# LiFePO4_Charger.net
KiCad netlist of a schematic drawn in EAGLE
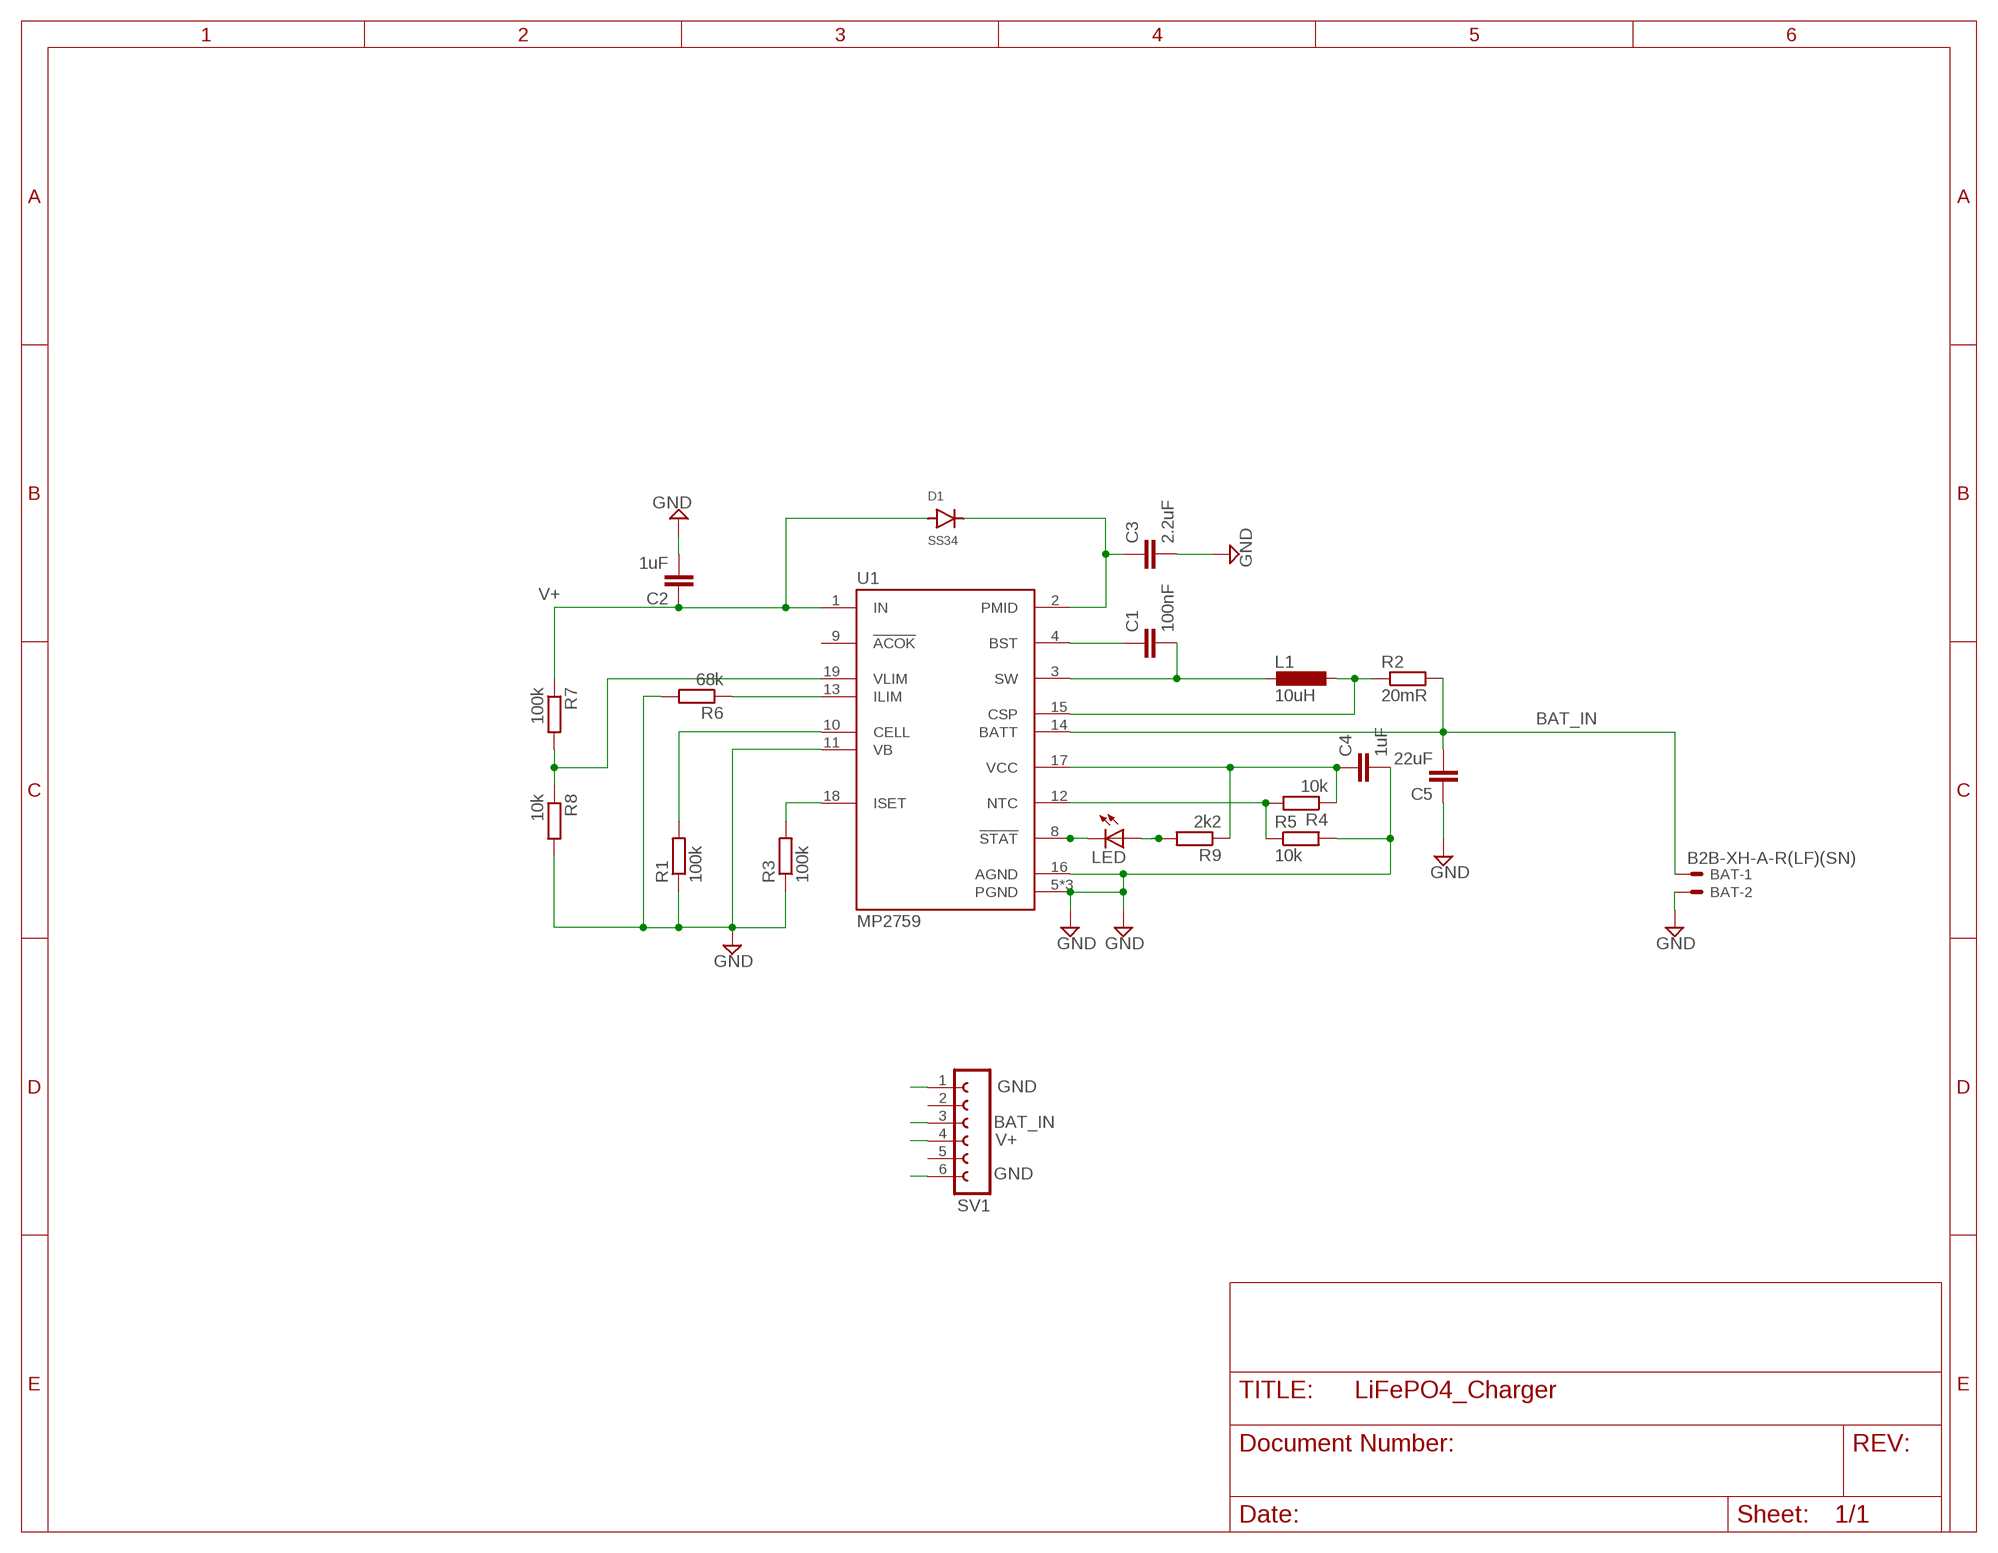
[diagram p0: schematic, sheet 1]

(export (version "E")
  (design (tool "Eeschema 10.0.6"))
  (components
    (comp (ref "BAT")
      (value "B2B-XH-A-R(LF)(SN)")
      (footprint "eagle-import:JST-XH-02-PACKAGE-LONG-PAD")
      (libsource (lib "eagle-import") (part "JST-XH-02-PIN-LONG-PAD"))
    )
    (comp (ref "C1")
      (value "100nF")
      (footprint "eagle-import:C0805")
      (libsource (lib "eagle-import") (part "C-EUC0805"))
    )
    (comp (ref "C2")
      (value "1uF")
      (footprint "eagle-import:C0805")
      (libsource (lib "eagle-import") (part "C-EUC0805"))
    )
    (comp (ref "C3")
      (value "2.2uF")
      (footprint "eagle-import:C0805")
      (libsource (lib "eagle-import") (part "C-EUC0805"))
    )
    (comp (ref "C4")
      (value "1uF")
      (footprint "eagle-import:C0805")
      (libsource (lib "eagle-import") (part "C-EUC0805"))
    )
    (comp (ref "C5")
      (value "22uF")
      (footprint "eagle-import:C0805")
      (libsource (lib "eagle-import") (part "C-EUC0805"))
    )
    (comp (ref "D1")
      (value "SS34")
      (footprint "eagle-import:SMA")
      (libsource (lib "eagle-import") (part "S1M"))
    )
    (comp (ref "L1")
      (value "10uH")
      (footprint "eagle-import:FXL0630-100-M")
      (libsource (lib "eagle-import") (part "FXL0630-100-M"))
    )
    (comp (ref "LED")
      (value "LEDCHIPLED_0805")
      (footprint "eagle-import:CHIPLED_0805")
      (libsource (lib "eagle-import") (part "LEDCHIPLED_0805"))
    )
    (comp (ref "R1")
      (value "100k")
      (footprint "eagle-import:R0603")
      (libsource (lib "eagle-import") (part "R-EU_R0603"))
    )
    (comp (ref "R2")
      (value "20mR")
      (footprint "eagle-import:R1206")
      (libsource (lib "eagle-import") (part "R-EU_R1206"))
    )
    (comp (ref "R3")
      (value "100k")
      (footprint "eagle-import:R0603")
      (libsource (lib "eagle-import") (part "R-EU_R0603"))
    )
    (comp (ref "R4")
      (value "10k")
      (footprint "eagle-import:R0603")
      (libsource (lib "eagle-import") (part "R-EU_R0603"))
    )
    (comp (ref "R5")
      (value "10k")
      (footprint "eagle-import:R0603")
      (libsource (lib "eagle-import") (part "R-EU_R0603"))
    )
    (comp (ref "R6")
      (value "68k")
      (footprint "eagle-import:R0603")
      (libsource (lib "eagle-import") (part "R-EU_R0603"))
    )
    (comp (ref "R7")
      (value "100k")
      (footprint "eagle-import:R0603")
      (libsource (lib "eagle-import") (part "R-EU_R0603"))
    )
    (comp (ref "R8")
      (value "10k")
      (footprint "eagle-import:R0603")
      (libsource (lib "eagle-import") (part "R-EU_R0603"))
    )
    (comp (ref "R9")
      (value "2k2")
      (footprint "eagle-import:R0603")
      (libsource (lib "eagle-import") (part "R-EU_R0603"))
    )
    (comp (ref "SV1")
      (value "FE06W")
      (footprint "eagle-import:FE06W")
      (libsource (lib "eagle-import") (part "FE06W"))
    )
    (comp (ref "U1")
      (value "MP2759")
      (footprint "eagle-import:IC_MP2759GQ-0000-P")
      (fields (field (name "MF") "Monolithic Power Systems Inc.") (field (name "MP") "MP2759GQ-0000-P"))
      (libsource (lib "eagle-import") (part "MP2759GQ-0000-P"))
    )
  )
  (nets
    (net (code "1") (name "/BAT_IN") (class "Default")
      (node (ref "BAT") (pin "1") (pinfunction "S_1") (pintype "passive"))
      (node (ref "C5") (pin "2") (pinfunction "2_2") (pintype "passive"))
      (node (ref "R2") (pin "2") (pinfunction "2_2") (pintype "passive"))
      (node (ref "SV1") (pin "3") (pinfunction "3_3") (pintype "passive"))
      (node (ref "U1") (pin "14") (pinfunction "BATT_14") (pintype "input"))
    )
    (net (code "2") (name "/V+") (class "Default")
      (node (ref "C2") (pin "1") (pinfunction "1_1") (pintype "passive"))
      (node (ref "D1") (pin "A") (pinfunction "A_A") (pintype "passive"))
      (node (ref "R7") (pin "1") (pinfunction "1_1") (pintype "passive"))
      (node (ref "SV1") (pin "4") (pinfunction "4_4") (pintype "passive"))
      (node (ref "U1") (pin "1") (pinfunction "IN_1") (pintype "input"))
    )
    (net (code "3") (name "GND") (class "Default")
      (node (ref "BAT") (pin "2") (pinfunction "S_2") (pintype "passive"))
      (node (ref "C2") (pin "2") (pinfunction "2_2") (pintype "passive"))
      (node (ref "C3") (pin "2") (pinfunction "2_2") (pintype "passive"))
      (node (ref "C4") (pin "2") (pinfunction "2_2") (pintype "passive"))
      (node (ref "C5") (pin "1") (pinfunction "1_1") (pintype "passive"))
      (node (ref "R1") (pin "1") (pinfunction "1_1") (pintype "passive"))
      (node (ref "R3") (pin "1") (pinfunction "1_1") (pintype "passive"))
      (node (ref "R5") (pin "2") (pinfunction "2_2") (pintype "passive"))
      (node (ref "R6") (pin "2") (pinfunction "2_2") (pintype "passive"))
      (node (ref "R8") (pin "2") (pinfunction "2_2") (pintype "passive"))
      (node (ref "SV1") (pin "1") (pinfunction "1_1") (pintype "passive"))
      (node (ref "SV1") (pin "6") (pinfunction "6_6") (pintype "passive"))
      (node (ref "U1") (pin "11") (pinfunction "VB_11") (pintype "input"))
      (node (ref "U1") (pin "16") (pinfunction "AGND_16") (pintype "power_in"))
      (node (ref "U1") (pin "5") (pinfunction "PGND_5") (pintype "power_in"))
      (node (ref "U1") (pin "6") (pinfunction "PGND_6") (pintype "power_in"))
      (node (ref "U1") (pin "7") (pinfunction "PGND_7") (pintype "power_in"))
    )
    (net (code "4") (name "Net-(L1-1)") (class "Default")
      (node (ref "C1") (pin "2") (pinfunction "2_2") (pintype "passive"))
      (node (ref "L1") (pin "P$1") (pinfunction "1_P$1") (pintype "passive"))
      (node (ref "U1") (pin "3") (pinfunction "SW_3") (pintype "passive"))
    )
    (net (code "5") (name "Net-(L1-2)") (class "Default")
      (node (ref "L1") (pin "P$2") (pinfunction "2_P$2") (pintype "passive"))
      (node (ref "R2") (pin "1") (pinfunction "1_1") (pintype "passive"))
      (node (ref "U1") (pin "15") (pinfunction "CSP_15") (pintype "input"))
    )
    (net (code "6") (name "Net-(LED-PadA)") (class "Default")
      (node (ref "LED") (pin "A") (pinfunction "A_A") (pintype "passive"))
      (node (ref "R9") (pin "2") (pinfunction "2_2") (pintype "passive"))
    )
    (net (code "7") (name "Net-(U1-BST)") (class "Default")
      (node (ref "C1") (pin "1") (pinfunction "1_1") (pintype "passive"))
      (node (ref "U1") (pin "4") (pinfunction "BST_4") (pintype "passive"))
    )
    (net (code "8") (name "Net-(U1-CELL)") (class "Default")
      (node (ref "R1") (pin "2") (pinfunction "2_2") (pintype "passive"))
      (node (ref "U1") (pin "10") (pinfunction "CELL_10") (pintype "input"))
    )
    (net (code "9") (name "Net-(U1-ILIM)") (class "Default")
      (node (ref "R6") (pin "1") (pinfunction "1_1") (pintype "passive"))
      (node (ref "U1") (pin "13") (pinfunction "ILIM_13") (pintype "input"))
    )
    (net (code "10") (name "Net-(U1-ISET)") (class "Default")
      (node (ref "R3") (pin "2") (pinfunction "2_2") (pintype "passive"))
      (node (ref "U1") (pin "18") (pinfunction "ISET_18") (pintype "input"))
    )
    (net (code "11") (name "Net-(U1-NTC)") (class "Default")
      (node (ref "R4") (pin "2") (pinfunction "2_2") (pintype "passive"))
      (node (ref "R5") (pin "1") (pinfunction "1_1") (pintype "passive"))
      (node (ref "U1") (pin "12") (pinfunction "NTC_12") (pintype "input"))
    )
    (net (code "12") (name "Net-(U1-PMID)") (class "Default")
      (node (ref "C3") (pin "1") (pinfunction "1_1") (pintype "passive"))
      (node (ref "D1") (pin "C") (pinfunction "C_C") (pintype "passive"))
      (node (ref "U1") (pin "2") (pinfunction "PMID_2") (pintype "passive"))
    )
    (net (code "13") (name "Net-(U1-VCC)") (class "Default")
      (node (ref "C4") (pin "1") (pinfunction "1_1") (pintype "passive"))
      (node (ref "R4") (pin "1") (pinfunction "1_1") (pintype "passive"))
      (node (ref "R9") (pin "1") (pinfunction "1_1") (pintype "passive"))
      (node (ref "U1") (pin "17") (pinfunction "VCC_17") (pintype "passive"))
    )
    (net (code "14") (name "Net-(U1-VLIM)") (class "Default")
      (node (ref "R7") (pin "2") (pinfunction "2_2") (pintype "passive"))
      (node (ref "R8") (pin "1") (pinfunction "1_1") (pintype "passive"))
      (node (ref "U1") (pin "19") (pinfunction "VLIM_19") (pintype "input"))
    )
    (net (code "15") (name "Net-(U1-~{STAT})") (class "Default")
      (node (ref "LED") (pin "C") (pinfunction "C_C") (pintype "passive"))
      (node (ref "U1") (pin "8") (pinfunction "~{STAT}_8") (pintype "output"))
    )
    (net (code "16") (name "unconnected-(SV1-Pad2)") (class "Default")
      (node (ref "SV1") (pin "2") (pinfunction "2_2") (pintype "passive"))
    )
    (net (code "17") (name "unconnected-(SV1-Pad5)") (class "Default")
      (node (ref "SV1") (pin "5") (pinfunction "5_5") (pintype "passive"))
    )
    (net (code "18") (name "unconnected-(U1-~{ACOK}-Pad9)") (class "Default")
      (node (ref "U1") (pin "9") (pinfunction "~{ACOK}_9") (pintype "output"))
    )
  )
)
